# wifi_03_12_2018.net
KiCad netlist of a schematic drawn in EAGLE
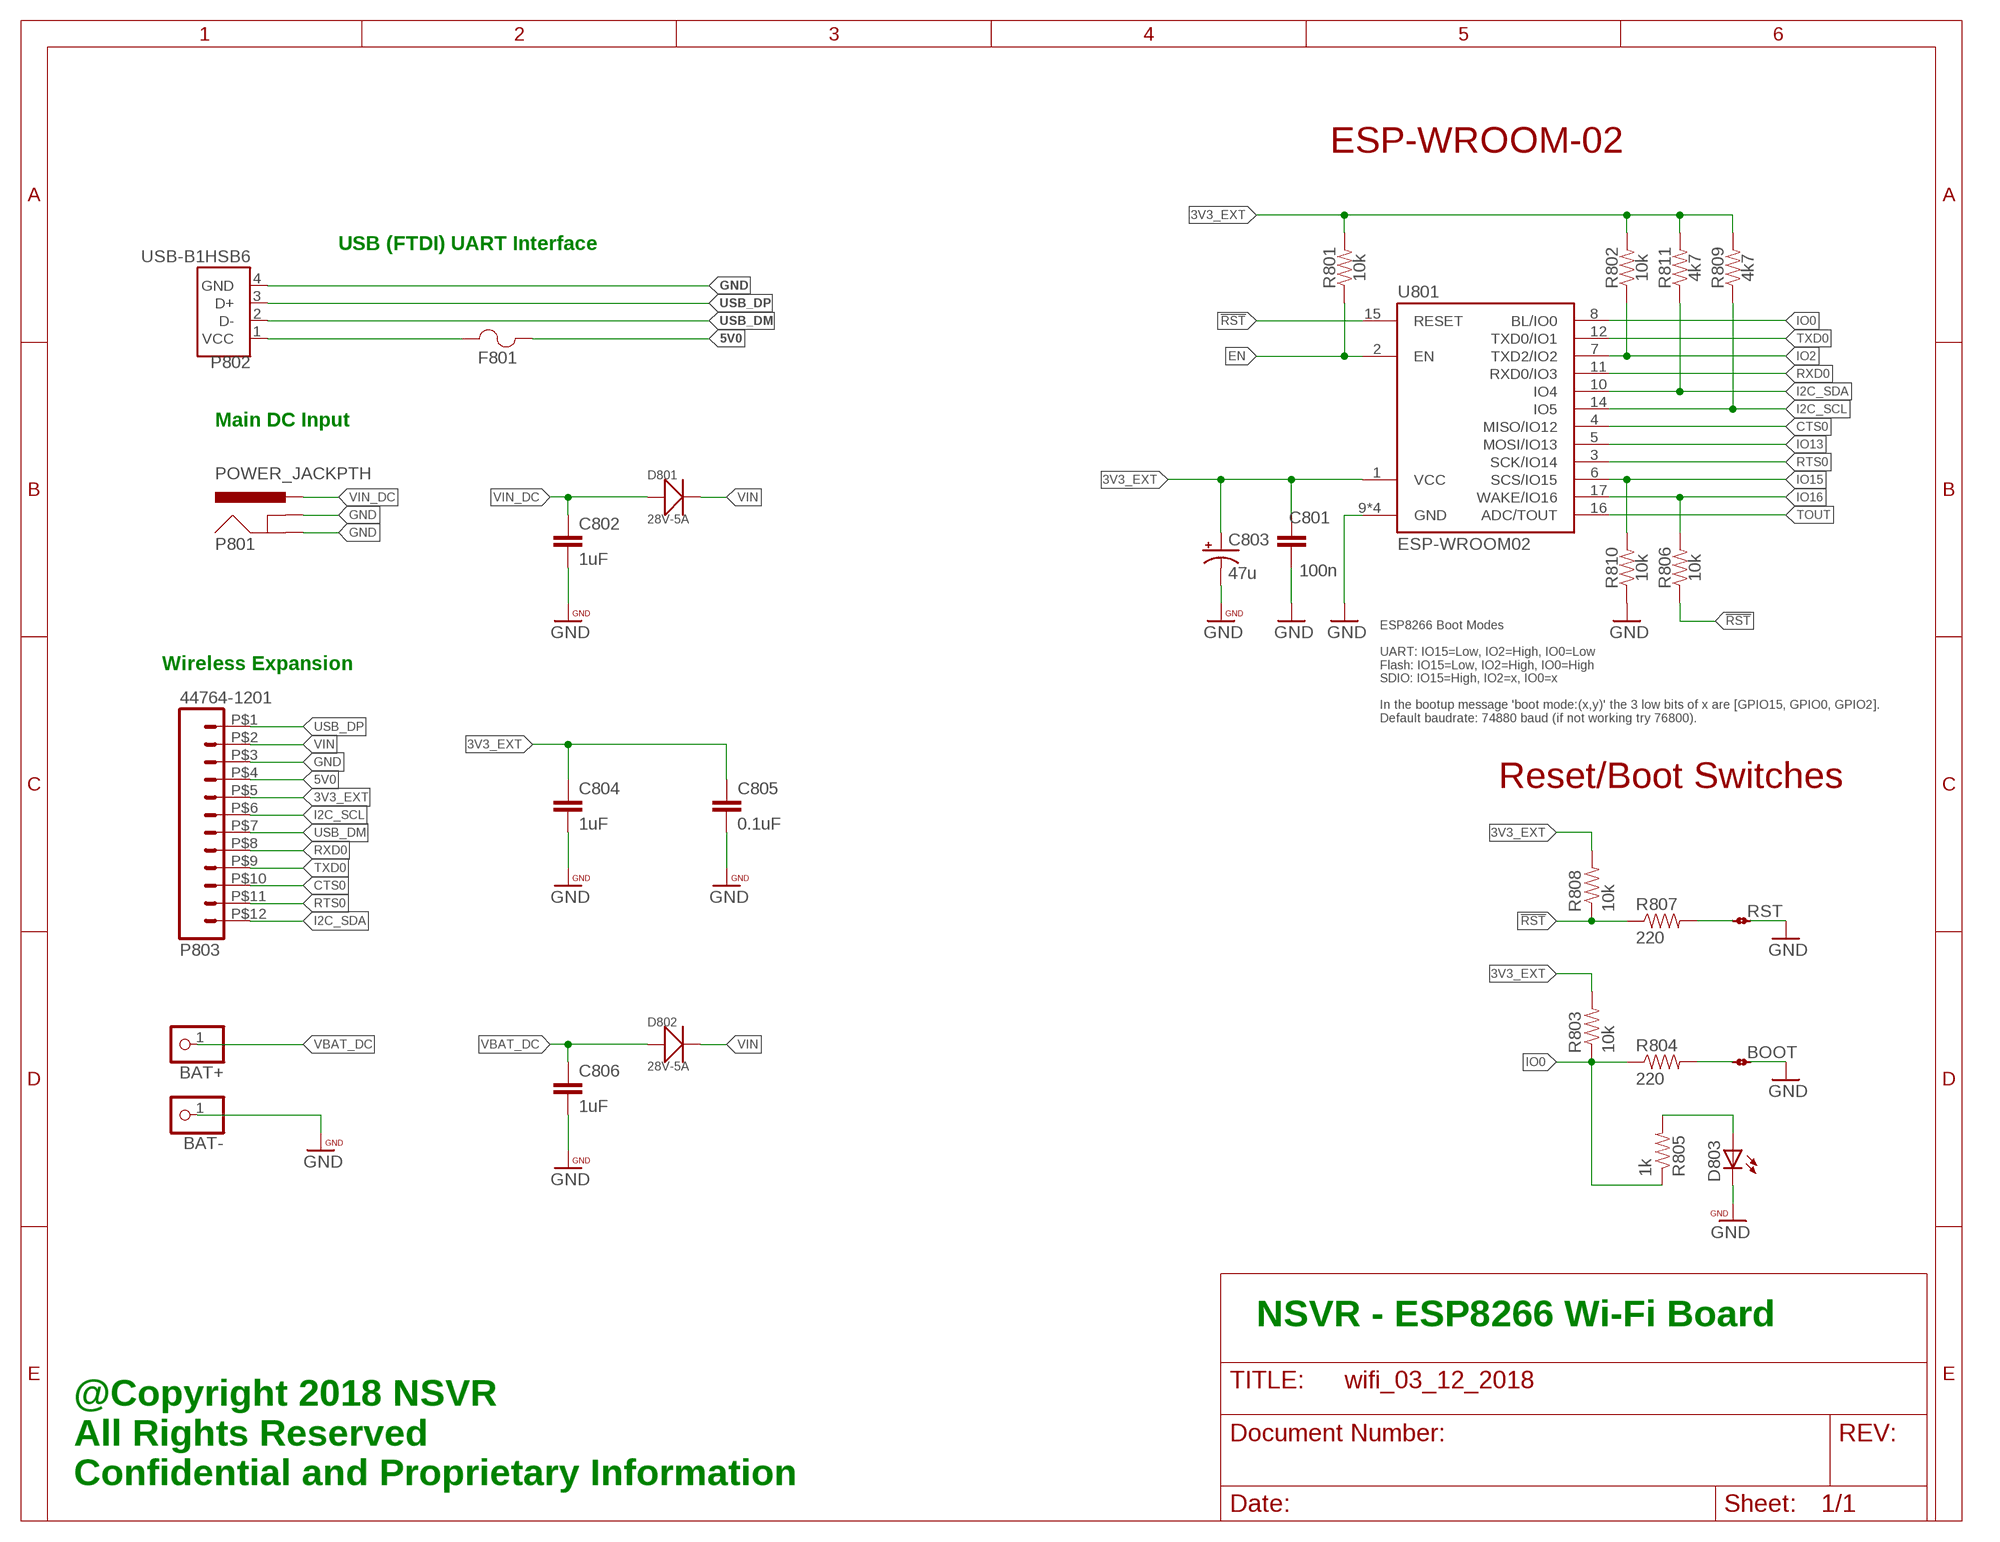
[diagram p0: schematic, sheet 1]

(export (version "E")
  (design (tool "Eeschema 10.0.6"))
  (components
    (comp (ref "BAT+")
      (value "WPAD-1-PTH")
      (footprint "eagle-import:WPAD-1-PTH-2.54")
      (libsource (lib "eagle-import") (part "WPAD-1-PTH"))
    )
    (comp (ref "BAT-")
      (value "WPAD-1-PTH")
      (footprint "eagle-import:WPAD-1-PTH-2.54")
      (libsource (lib "eagle-import") (part "WPAD-1-PTH"))
    )
    (comp (ref "BOOT")
      (value "JMP-2-NO-PTH")
      (footprint "eagle-import:JMP-2-NO-PTH-2.54")
      (libsource (lib "eagle-import") (part "JMP-2-NO-PTH"))
    )
    (comp (ref "C801")
      (value "100n")
      (footprint "eagle-import:0402-CAP")
      (libsource (lib "eagle-import") (part "CAP0402-CAP"))
    )
    (comp (ref "C802")
      (value "1uF")
      (footprint "eagle-import:0402-CAP")
      (libsource (lib "eagle-import") (part "CAP0402-CAP"))
    )
    (comp (ref "C803")
      (value "47u")
      (footprint "eagle-import:PANASONIC_D")
      (libsource (lib "eagle-import") (part "CAP_POLD"))
    )
    (comp (ref "C804")
      (value "1uF")
      (footprint "eagle-import:0402-CAP")
      (libsource (lib "eagle-import") (part "CAP0402-CAP"))
    )
    (comp (ref "C805")
      (value "0.1uF")
      (footprint "eagle-import:0402-CAP")
      (libsource (lib "eagle-import") (part "CAP0402-CAP"))
    )
    (comp (ref "C806")
      (value "1uF")
      (footprint "eagle-import:0402-CAP")
      (libsource (lib "eagle-import") (part "CAP0402-CAP"))
    )
    (comp (ref "D801")
      (value "28V-5A")
      (footprint "eagle-import:DO-214AA")
      (fields (field (name "MPN") "SS54B"))
      (libsource (lib "eagle-import") (part "SMD-DIODE-SCHOTTKY-28V-5A(DO-214AA)"))
    )
    (comp (ref "D802")
      (value "28V-5A")
      (footprint "eagle-import:DO-214AA")
      (fields (field (name "MPN") "SS54B"))
      (libsource (lib "eagle-import") (part "SMD-DIODE-SCHOTTKY-28V-5A(DO-214AA)"))
    )
    (comp (ref "D803")
      (value "LEDCHIP-LED0603")
      (footprint "eagle-import:CHIP-LED0603")
      (libsource (lib "eagle-import") (part "LEDCHIP-LED0603"))
    )
    (comp (ref "F801")
      (value "1206L050YR")
      (footprint "eagle-import:1206LSERIES")
      (fields (field (name "COPYRIGHT") "Copyright C 2015 Accelerated Designs. All rights reserved"))
      (libsource (lib "eagle-import") (part "1206L050YR"))
    )
    (comp (ref "P801")
      (value "POWER_JACKPTH")
      (footprint "eagle-import:POWER_JACK_PTH")
      (libsource (lib "eagle-import") (part "POWER_JACKPTH"))
    )
    (comp (ref "P802")
      (value "USB-B1HSB6")
      (footprint "eagle-import:OST_USB-B1HSB6")
      (fields (field (name "MF") "On Shore Technology"))
      (libsource (lib "eagle-import") (part "USB-B1HSB6"))
    )
    (comp (ref "P803")
      (value "44764-1201")
      (footprint "eagle-import:44764-1201")
      (libsource (lib "eagle-import") (part "44764-1201"))
    )
    (comp (ref "R801")
      (value "10k")
      (footprint "eagle-import:EIA-0402")
      (libsource (lib "eagle-import") (part "RESISTOR0402-TYP"))
    )
    (comp (ref "R802")
      (value "10k")
      (footprint "eagle-import:EIA-0402")
      (libsource (lib "eagle-import") (part "RESISTOR0402-TYP"))
    )
    (comp (ref "R803")
      (value "10k")
      (footprint "eagle-import:EIA-0402")
      (libsource (lib "eagle-import") (part "RESISTOR0402-TYP"))
    )
    (comp (ref "R804")
      (value "220")
      (footprint "eagle-import:EIA-0402")
      (libsource (lib "eagle-import") (part "RESISTOR0402-TYP"))
    )
    (comp (ref "R805")
      (value "1k")
      (footprint "eagle-import:EIA-0402")
      (libsource (lib "eagle-import") (part "RESISTOR0402-TYP"))
    )
    (comp (ref "R806")
      (value "10k")
      (footprint "eagle-import:EIA-0402")
      (libsource (lib "eagle-import") (part "RESISTOR0402-TYP"))
    )
    (comp (ref "R807")
      (value "220")
      (footprint "eagle-import:EIA-0402")
      (libsource (lib "eagle-import") (part "RESISTOR0402-TYP"))
    )
    (comp (ref "R808")
      (value "10k")
      (footprint "eagle-import:EIA-0402")
      (libsource (lib "eagle-import") (part "RESISTOR0402-TYP"))
    )
    (comp (ref "R809")
      (value "4k7")
      (footprint "eagle-import:EIA-0402")
      (libsource (lib "eagle-import") (part "RESISTOR0402-TYP"))
    )
    (comp (ref "R810")
      (value "10k")
      (footprint "eagle-import:EIA-0402")
      (libsource (lib "eagle-import") (part "RESISTOR0402-TYP"))
    )
    (comp (ref "R811")
      (value "4k7")
      (footprint "eagle-import:EIA-0402")
      (libsource (lib "eagle-import") (part "RESISTOR0402-TYP"))
    )
    (comp (ref "RST")
      (value "JMP-2-NO-PTH")
      (footprint "eagle-import:JMP-2-NO-PTH-2.54")
      (libsource (lib "eagle-import") (part "JMP-2-NO-PTH"))
    )
    (comp (ref "U801")
      (value "ESP-WROOM02")
      (footprint "eagle-import:ESP-WROOM02")
      (libsource (lib "eagle-import") (part "ESP-WROOM02"))
    )
  )
  (nets
    (net (code "1") (name "/~{RST}") (class "Default")
      (node (ref "R806") (pin "1") (pinfunction "1_1") (pintype "passive"))
      (node (ref "R807") (pin "1") (pinfunction "1_1") (pintype "passive"))
      (node (ref "R808") (pin "1") (pinfunction "1_1") (pintype "passive"))
      (node (ref "U801") (pin "15") (pinfunction "RESET_15") (pintype "bidirectional"))
    )
    (net (code "2") (name "3V3_EXT") (class "Default")
      (node (ref "C801") (pin "2") (pinfunction "2_2") (pintype "passive"))
      (node (ref "C803") (pin "+") (pinfunction "+_+") (pintype "passive"))
      (node (ref "C804") (pin "1") (pinfunction "1_1") (pintype "passive"))
      (node (ref "C805") (pin "1") (pinfunction "1_1") (pintype "passive"))
      (node (ref "P803") (pin "P$5") (pinfunction "5_P$5") (pintype "passive"))
      (node (ref "R801") (pin "2") (pinfunction "2_2") (pintype "passive"))
      (node (ref "R802") (pin "2") (pinfunction "2_2") (pintype "passive"))
      (node (ref "R803") (pin "2") (pinfunction "2_2") (pintype "passive"))
      (node (ref "R808") (pin "2") (pinfunction "2_2") (pintype "passive"))
      (node (ref "R809") (pin "2") (pinfunction "2_2") (pintype "passive"))
      (node (ref "R811") (pin "2") (pinfunction "2_2") (pintype "passive"))
      (node (ref "U801") (pin "1") (pinfunction "VCC_1") (pintype "power_in"))
    )
    (net (code "3") (name "5V0") (class "Default")
      (node (ref "F801") (pin "2") (pinfunction "2_2") (pintype "passive"))
      (node (ref "P803") (pin "P$4") (pinfunction "4_P$4") (pintype "passive"))
    )
    (net (code "4") (name "CTS0") (class "Default")
      (node (ref "P803") (pin "P$10") (pinfunction "10_P$10") (pintype "passive"))
      (node (ref "U801") (pin "4") (pinfunction "MISO/IO12_4") (pintype "bidirectional"))
    )
    (net (code "5") (name "EN") (class "Default")
      (node (ref "R801") (pin "1") (pinfunction "1_1") (pintype "passive"))
      (node (ref "U801") (pin "2") (pinfunction "EN_2") (pintype "bidirectional"))
    )
    (net (code "6") (name "GND") (class "Default")
      (node (ref "BAT-") (pin "1") (pinfunction "1_1") (pintype "passive"))
      (node (ref "BOOT") (pin "2") (pinfunction "2_2") (pintype "passive"))
      (node (ref "C801") (pin "1") (pinfunction "1_1") (pintype "passive"))
      (node (ref "C802") (pin "2") (pinfunction "2_2") (pintype "passive"))
      (node (ref "C803") (pin "-") (pinfunction "-_-") (pintype "passive"))
      (node (ref "C804") (pin "2") (pinfunction "2_2") (pintype "passive"))
      (node (ref "C805") (pin "2") (pinfunction "2_2") (pintype "passive"))
      (node (ref "C806") (pin "2") (pinfunction "2_2") (pintype "passive"))
      (node (ref "D803") (pin "C") (pinfunction "C_C") (pintype "passive"))
      (node (ref "P801") (pin "GND") (pinfunction "GND_GND") (pintype "bidirectional"))
      (node (ref "P801") (pin "GNDBREAK") (pinfunction "GNDBREAK_GNDBREAK") (pintype "bidirectional"))
      (node (ref "P802") (pin "4") (pinfunction "GND_4") (pintype "power_in"))
      (node (ref "P803") (pin "P$3") (pinfunction "3_P$3") (pintype "passive"))
      (node (ref "R810") (pin "1") (pinfunction "1_1") (pintype "passive"))
      (node (ref "RST") (pin "2") (pinfunction "2_2") (pintype "passive"))
      (node (ref "U801") (pin "13") (pinfunction "GND_13") (pintype "power_in"))
      (node (ref "U801") (pin "18") (pinfunction "GND_18") (pintype "power_in"))
      (node (ref "U801") (pin "9") (pinfunction "GND_9") (pintype "power_in"))
      (node (ref "U801") (pin "TP") (pinfunction "GND_TP") (pintype "power_in"))
    )
    (net (code "7") (name "I2C_SCL") (class "Default")
      (node (ref "P803") (pin "P$6") (pinfunction "6_P$6") (pintype "passive"))
      (node (ref "R809") (pin "1") (pinfunction "1_1") (pintype "passive"))
      (node (ref "U801") (pin "14") (pinfunction "IO5_14") (pintype "bidirectional"))
    )
    (net (code "8") (name "I2C_SDA") (class "Default")
      (node (ref "P803") (pin "P$12") (pinfunction "12_P$12") (pintype "passive"))
      (node (ref "R811") (pin "1") (pinfunction "1_1") (pintype "passive"))
      (node (ref "U801") (pin "10") (pinfunction "IO4_10") (pintype "bidirectional"))
    )
    (net (code "9") (name "IO0") (class "Default")
      (node (ref "R803") (pin "1") (pinfunction "1_1") (pintype "passive"))
      (node (ref "R804") (pin "1") (pinfunction "1_1") (pintype "passive"))
      (node (ref "R805") (pin "1") (pinfunction "1_1") (pintype "passive"))
      (node (ref "U801") (pin "8") (pinfunction "BL/IO0_8") (pintype "bidirectional"))
    )
    (net (code "10") (name "IO2") (class "Default")
      (node (ref "R802") (pin "1") (pinfunction "1_1") (pintype "passive"))
      (node (ref "U801") (pin "7") (pinfunction "TXD2/IO2_7") (pintype "bidirectional"))
    )
    (net (code "11") (name "IO13") (class "Default")
      (node (ref "U801") (pin "5") (pinfunction "MOSI/IO13_5") (pintype "bidirectional"))
    )
    (net (code "12") (name "IO15") (class "Default")
      (node (ref "R810") (pin "2") (pinfunction "2_2") (pintype "passive"))
      (node (ref "U801") (pin "6") (pinfunction "SCS/IO15_6") (pintype "bidirectional"))
    )
    (net (code "13") (name "IO16") (class "Default")
      (node (ref "R806") (pin "2") (pinfunction "2_2") (pintype "passive"))
      (node (ref "U801") (pin "17") (pinfunction "WAKE/IO16_17") (pintype "bidirectional"))
    )
    (net (code "14") (name "Net-(BOOT-Pad1)") (class "Default")
      (node (ref "BOOT") (pin "1") (pinfunction "1_1") (pintype "passive"))
      (node (ref "R804") (pin "2") (pinfunction "2_2") (pintype "passive"))
    )
    (net (code "15") (name "Net-(D803-PadA)") (class "Default")
      (node (ref "D803") (pin "A") (pinfunction "A_A") (pintype "passive"))
      (node (ref "R805") (pin "2") (pinfunction "2_2") (pintype "passive"))
    )
    (net (code "16") (name "Net-(P802-VCC)") (class "Default")
      (node (ref "F801") (pin "1") (pinfunction "1_1") (pintype "passive"))
      (node (ref "P802") (pin "1") (pinfunction "VCC_1") (pintype "power_in"))
    )
    (net (code "17") (name "Net-(R807-Pad2)") (class "Default")
      (node (ref "R807") (pin "2") (pinfunction "2_2") (pintype "passive"))
      (node (ref "RST") (pin "1") (pinfunction "1_1") (pintype "passive"))
    )
    (net (code "18") (name "RTS0") (class "Default")
      (node (ref "P803") (pin "P$11") (pinfunction "11_P$11") (pintype "passive"))
      (node (ref "U801") (pin "3") (pinfunction "SCK/IO14_3") (pintype "bidirectional"))
    )
    (net (code "19") (name "RXD0") (class "Default")
      (node (ref "P803") (pin "P$8") (pinfunction "8_P$8") (pintype "passive"))
      (node (ref "U801") (pin "11") (pinfunction "RXD0/IO3_11") (pintype "bidirectional"))
    )
    (net (code "20") (name "TOUT") (class "Default")
      (node (ref "U801") (pin "16") (pinfunction "ADC/TOUT_16") (pintype "bidirectional"))
    )
    (net (code "21") (name "TXD0") (class "Default")
      (node (ref "P803") (pin "P$9") (pinfunction "9_P$9") (pintype "passive"))
      (node (ref "U801") (pin "12") (pinfunction "TXD0/IO1_12") (pintype "bidirectional"))
    )
    (net (code "22") (name "USB_DM") (class "Default")
      (node (ref "P802") (pin "2") (pinfunction "D-_2") (pintype "bidirectional"))
      (node (ref "P803") (pin "P$7") (pinfunction "7_P$7") (pintype "passive"))
    )
    (net (code "23") (name "USB_DP") (class "Default")
      (node (ref "P802") (pin "3") (pinfunction "D+_3") (pintype "bidirectional"))
      (node (ref "P803") (pin "P$1") (pinfunction "1_P$1") (pintype "passive"))
    )
    (net (code "24") (name "VBAT_DC") (class "Default")
      (node (ref "BAT+") (pin "1") (pinfunction "1_1") (pintype "passive"))
      (node (ref "C806") (pin "1") (pinfunction "1_1") (pintype "passive"))
      (node (ref "D802") (pin "+") (pinfunction "+_+") (pintype "passive"))
    )
    (net (code "25") (name "VIN") (class "Default")
      (node (ref "D801") (pin "-") (pinfunction "-_-") (pintype "passive"))
      (node (ref "D802") (pin "-") (pinfunction "-_-") (pintype "passive"))
      (node (ref "P803") (pin "P$2") (pinfunction "2_P$2") (pintype "passive"))
    )
    (net (code "26") (name "VIN_DC") (class "Default")
      (node (ref "C802") (pin "1") (pinfunction "1_1") (pintype "passive"))
      (node (ref "D801") (pin "+") (pinfunction "+_+") (pintype "passive"))
      (node (ref "P801") (pin "PWR") (pinfunction "PWR_PWR") (pintype "bidirectional"))
    )
  )
)
